# Lumen-Driver-X2.net
KiCad netlist of a schematic drawn in EAGLE
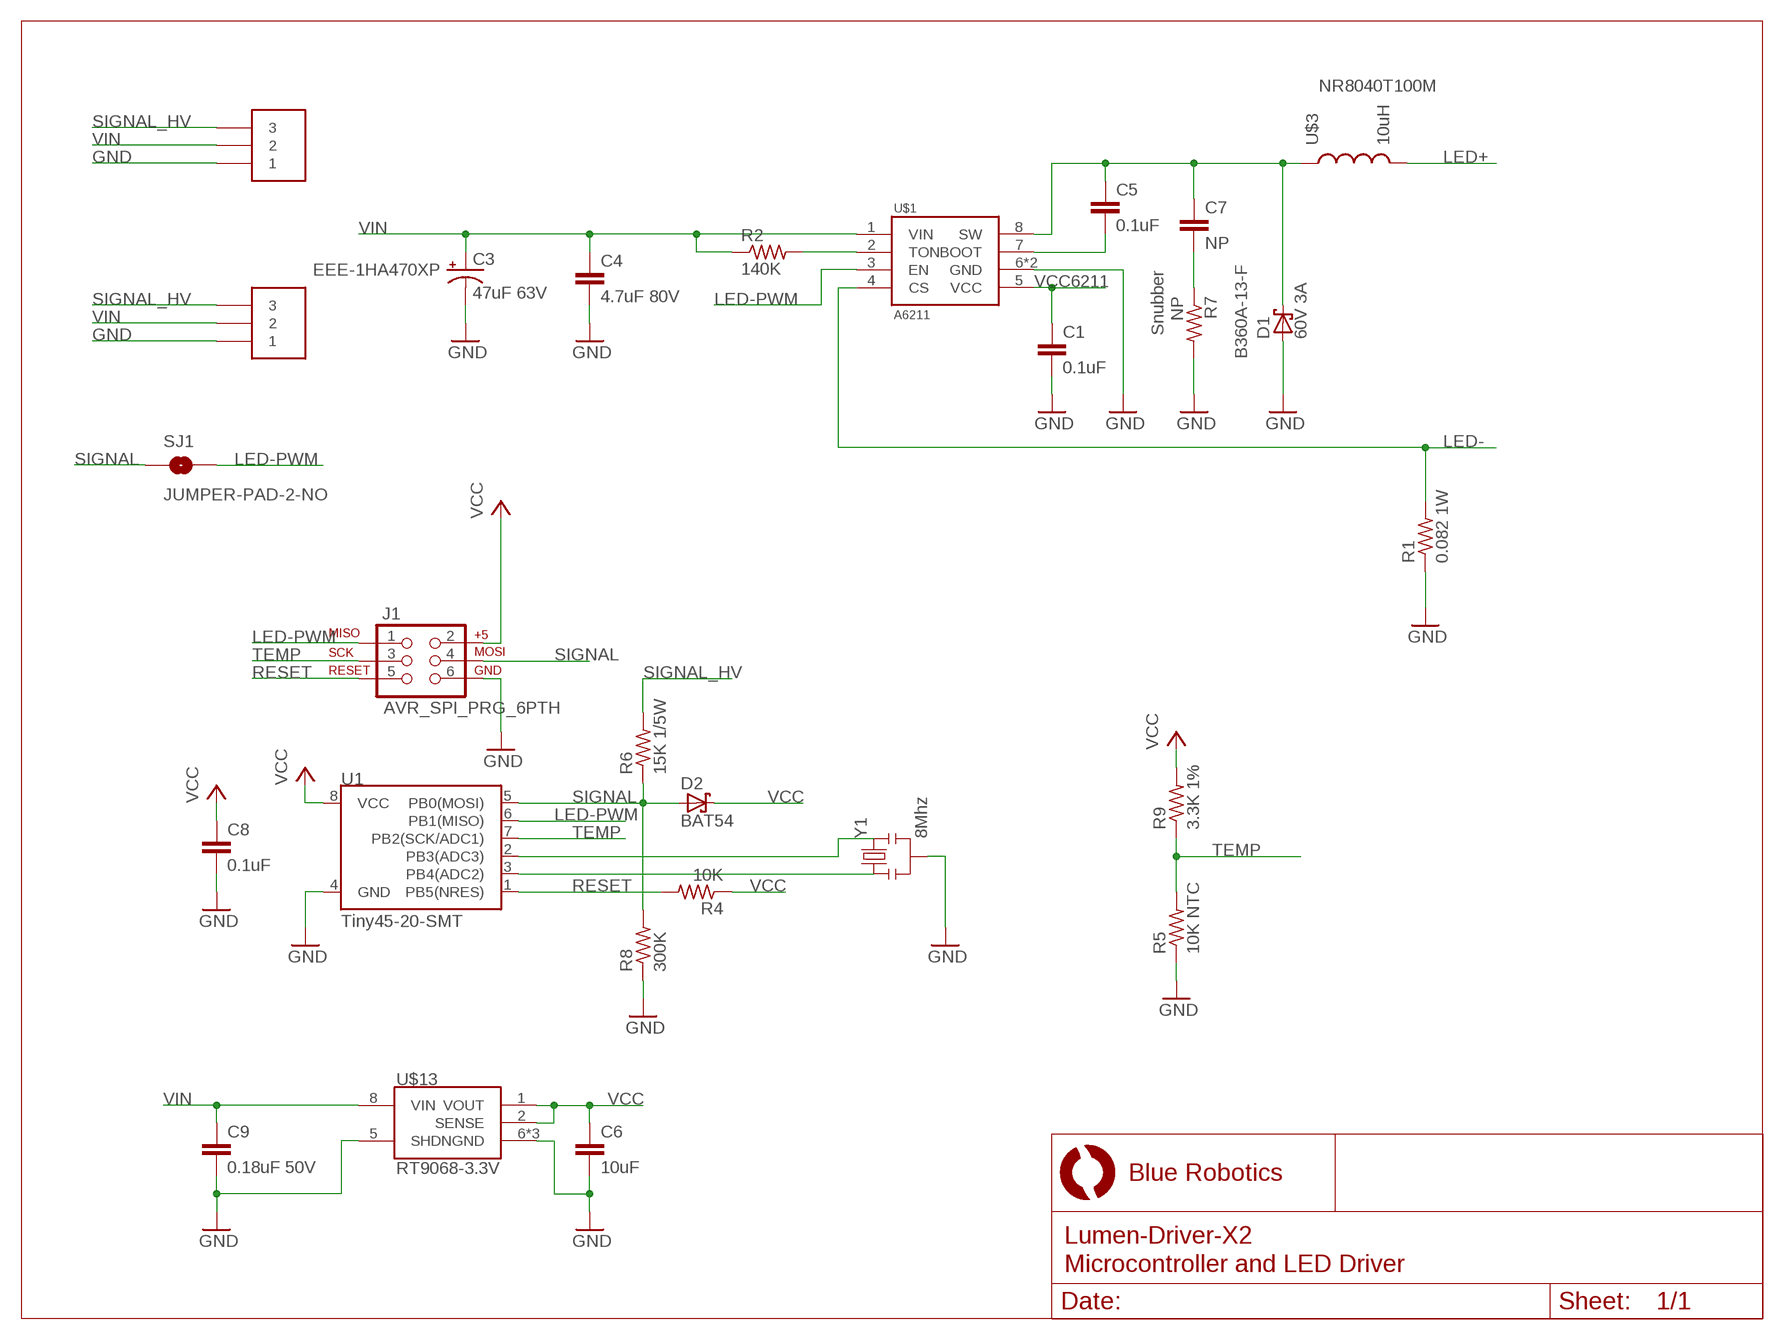
[diagram p0: schematic, sheet 1]

(export (version "E")
  (design (tool "Eeschema 10.0.6"))
  (components
    (comp (ref "C1")
      (value "0.1uF")
      (footprint "eagle-import:C0402")
      (libsource (lib "eagle-import") (part "CAPACITOR_0402"))
    )
    (comp (ref "C3")
      (value "47uF 63V")
      (footprint "eagle-import:PANASONIC_D")
      (libsource (lib "eagle-import") (part "CAP_POLD"))
    )
    (comp (ref "C4")
      (value "4.7uF 80V")
      (footprint "eagle-import:C1210")
      (libsource (lib "eagle-import") (part "C-EUC1210"))
    )
    (comp (ref "C5")
      (value "0.1uF")
      (footprint "eagle-import:C0402")
      (libsource (lib "eagle-import") (part "CAPACITOR_0402"))
    )
    (comp (ref "C6")
      (value "10uF")
      (footprint "eagle-import:C0603")
      (libsource (lib "eagle-import") (part "C-EUC0603"))
    )
    (comp (ref "C7")
      (value "NP")
      (footprint "eagle-import:C0603")
      (libsource (lib "eagle-import") (part "C-EUC0603"))
    )
    (comp (ref "C8")
      (value "0.1uF")
      (footprint "eagle-import:C0402")
      (libsource (lib "eagle-import") (part "CAPACITOR_0402"))
    )
    (comp (ref "C9")
      (value "0.18uF 50V")
      (footprint "eagle-import:C0805")
      (libsource (lib "eagle-import") (part "C-EUC0805"))
    )
    (comp (ref "D1")
      (value "60V 3A")
      (footprint "eagle-import:SMA")
      (libsource (lib "eagle-import") (part "DIODE-SCHOTTKYSMA"))
    )
    (comp (ref "D2")
      (value "BAT54")
      (footprint "eagle-import:SOD523")
      (libsource (lib "eagle-import") (part "DIODE-SCHOTTKYSOD523"))
    )
    (comp (ref "J1")
      (value "AVR_SPI_PRG_6PTH")
      (footprint "eagle-import:2X3")
      (libsource (lib "eagle-import") (part "AVR_SPI_PRG_6PTH"))
    )
    (comp (ref "R1")
      (value "0.082 1W")
      (footprint "eagle-import:R2512")
      (libsource (lib "eagle-import") (part "R-US_R2512"))
    )
    (comp (ref "R2")
      (value "140K")
      (footprint "eagle-import:R0402")
      (libsource (lib "eagle-import") (part "RESISTOR_0402"))
    )
    (comp (ref "R4")
      (value "10K")
      (footprint "eagle-import:R0402")
      (libsource (lib "eagle-import") (part "RESISTOR_0402"))
    )
    (comp (ref "R5")
      (value "10K NTC")
      (footprint "eagle-import:R0603")
      (libsource (lib "eagle-import") (part "R-US_R0603"))
    )
    (comp (ref "R6")
      (value "15K 1/5W")
      (footprint "eagle-import:R0402")
      (libsource (lib "eagle-import") (part "RESISTOR_0402"))
    )
    (comp (ref "R7")
      (value "NP")
      (footprint "eagle-import:R1206")
      (libsource (lib "eagle-import") (part "R-US_R1206"))
    )
    (comp (ref "R8")
      (value "300K")
      (footprint "eagle-import:R0402")
      (libsource (lib "eagle-import") (part "RESISTOR_0402"))
    )
    (comp (ref "R9")
      (value "3.3K 1%")
      (footprint "eagle-import:R0402")
      (libsource (lib "eagle-import") (part "RESISTOR_0402"))
    )
    (comp (ref "SJ1")
      (value "JUMPER-PAD-2-NO")
      (footprint "eagle-import:PAD-JUMPER-2-NO_NO_SILK")
      (libsource (lib "eagle-import") (part "JUMPER-PAD-2-NO"))
    )
    (comp (ref "U$1")
      (value "A6211")
      (footprint "eagle-import:SOIC8N-LJ")
      (libsource (lib "eagle-import") (part "A6211"))
    )
    (comp (ref "U$3")
      (value "10uH")
      (footprint "eagle-import:INDUCTOR-8040")
      (libsource (lib "eagle-import") (part "INDUCTOR8040"))
    )
    (comp (ref "U$11")
      (value "009176003032006")
      (footprint "eagle-import:AVX-9176-3POS")
      (libsource (lib "eagle-import") (part "HEADER-3AVX-9176"))
    )
    (comp (ref "U$12")
      (value "009176003032006")
      (footprint "eagle-import:AVX-9176-3POS")
      (libsource (lib "eagle-import") (part "HEADER-3AVX-9176"))
    )
    (comp (ref "U$13")
      (value "RT9068-3.3V")
      (footprint "eagle-import:SOIC8N-LJ")
      (libsource (lib "eagle-import") (part "VREG-RT9068SOP-8"))
    )
    (comp (ref "U1")
      (value "Tiny45-20-SMT")
      (footprint "eagle-import:SO08-EIAJ")
      (libsource (lib "eagle-import") (part "ATTINY45TINY45-20-SMT"))
    )
    (comp (ref "Y1")
      (value "8Mhz")
      (footprint "eagle-import:RESONATOR-SMD")
      (libsource (lib "eagle-import") (part "RESONATORSMD"))
    )
  )
  (nets
    (net (code "1") (name "/LED+") (class "Default")
      (node (ref "U$3") (pin "P$2") (pinfunction "2_P$2") (pintype "passive"))
    )
    (net (code "2") (name "/LED-") (class "Default")
      (node (ref "R1") (pin "2") (pinfunction "2_2") (pintype "passive"))
      (node (ref "U$1") (pin "4") (pinfunction "CS_4") (pintype "bidirectional"))
    )
    (net (code "3") (name "/LED-PWM") (class "Default")
      (node (ref "J1") (pin "1") (pinfunction "1_1") (pintype "passive"))
      (node (ref "SJ1") (pin "2") (pinfunction "2_2") (pintype "passive"))
      (node (ref "U$1") (pin "3") (pinfunction "EN_3") (pintype "bidirectional"))
      (node (ref "U1") (pin "6") (pinfunction "PB1(MISO)_6") (pintype "bidirectional"))
    )
    (net (code "4") (name "/RESET") (class "Default")
      (node (ref "J1") (pin "5") (pinfunction "5_5") (pintype "passive"))
      (node (ref "R4") (pin "2") (pinfunction "2_2") (pintype "passive"))
      (node (ref "U1") (pin "1") (pinfunction "PB5(NRES)_1") (pintype "bidirectional"))
    )
    (net (code "5") (name "/SIGNAL") (class "Default")
      (node (ref "D2") (pin "A") (pinfunction "A_A") (pintype "passive"))
      (node (ref "J1") (pin "4") (pinfunction "4_4") (pintype "passive"))
      (node (ref "R6") (pin "1") (pinfunction "1_1") (pintype "passive"))
      (node (ref "R8") (pin "2") (pinfunction "2_2") (pintype "passive"))
      (node (ref "SJ1") (pin "1") (pinfunction "1_1") (pintype "passive"))
      (node (ref "U1") (pin "5") (pinfunction "PB0(MOSI)_5") (pintype "bidirectional"))
    )
    (net (code "6") (name "/SIGNAL_HV") (class "Default")
      (node (ref "R6") (pin "2") (pinfunction "2_2") (pintype "passive"))
      (node (ref "U$11") (pin "3") (pinfunction "3_3") (pintype "bidirectional"))
      (node (ref "U$12") (pin "3") (pinfunction "3_3") (pintype "bidirectional"))
    )
    (net (code "7") (name "/TEMP") (class "Default")
      (node (ref "J1") (pin "3") (pinfunction "3_3") (pintype "passive"))
      (node (ref "R5") (pin "2") (pinfunction "2_2") (pintype "passive"))
      (node (ref "R9") (pin "1") (pinfunction "1_1") (pintype "passive"))
      (node (ref "U1") (pin "7") (pinfunction "PB2(SCK/ADC1)_7") (pintype "bidirectional"))
    )
    (net (code "8") (name "/VCC6211") (class "Default")
      (node (ref "C1") (pin "1") (pinfunction "1_1") (pintype "passive"))
      (node (ref "U$1") (pin "5") (pinfunction "VCC_5") (pintype "bidirectional"))
    )
    (net (code "9") (name "/VIN") (class "Default")
      (node (ref "C3") (pin "+") (pinfunction "+_+") (pintype "passive"))
      (node (ref "C4") (pin "1") (pinfunction "1_1") (pintype "passive"))
      (node (ref "C9") (pin "1") (pinfunction "1_1") (pintype "passive"))
      (node (ref "R2") (pin "1") (pinfunction "1_1") (pintype "passive"))
      (node (ref "U$1") (pin "1") (pinfunction "VIN_1") (pintype "bidirectional"))
      (node (ref "U$11") (pin "2") (pinfunction "2_2") (pintype "bidirectional"))
      (node (ref "U$12") (pin "2") (pinfunction "2_2") (pintype "bidirectional"))
      (node (ref "U$13") (pin "8") (pinfunction "VIN_8") (pintype "bidirectional"))
    )
    (net (code "10") (name "GND") (class "Default")
      (node (ref "C1") (pin "2") (pinfunction "2_2") (pintype "passive"))
      (node (ref "C3") (pin "-") (pinfunction "-_-") (pintype "passive"))
      (node (ref "C4") (pin "2") (pinfunction "2_2") (pintype "passive"))
      (node (ref "C6") (pin "2") (pinfunction "2_2") (pintype "passive"))
      (node (ref "C8") (pin "2") (pinfunction "2_2") (pintype "passive"))
      (node (ref "C9") (pin "2") (pinfunction "2_2") (pintype "passive"))
      (node (ref "D1") (pin "A") (pinfunction "A_A") (pintype "passive"))
      (node (ref "J1") (pin "6") (pinfunction "6_6") (pintype "passive"))
      (node (ref "R1") (pin "1") (pinfunction "1_1") (pintype "passive"))
      (node (ref "R5") (pin "1") (pinfunction "1_1") (pintype "passive"))
      (node (ref "R7") (pin "2") (pinfunction "2_2") (pintype "passive"))
      (node (ref "R8") (pin "1") (pinfunction "1_1") (pintype "passive"))
      (node (ref "U$1") (pin "6") (pinfunction "GND_6") (pintype "bidirectional"))
      (node (ref "U$1") (pin "PAD") (pinfunction "GND_PAD") (pintype "bidirectional"))
      (node (ref "U$11") (pin "1") (pinfunction "1_1") (pintype "bidirectional"))
      (node (ref "U$12") (pin "1") (pinfunction "1_1") (pintype "bidirectional"))
      (node (ref "U$13") (pin "5") (pinfunction "SHDN_5") (pintype "bidirectional"))
      (node (ref "U$13") (pin "6") (pinfunction "GND_6") (pintype "bidirectional"))
      (node (ref "U$13") (pin "7") (pinfunction "GND_7") (pintype "bidirectional"))
      (node (ref "U$13") (pin "PAD") (pinfunction "GND_PAD") (pintype "bidirectional"))
      (node (ref "U1") (pin "4") (pinfunction "GND_4") (pintype "bidirectional"))
      (node (ref "Y1") (pin "2") (pinfunction "2_2") (pintype "passive"))
    )
    (net (code "11") (name "Net-(C7-Pad2)") (class "Default")
      (node (ref "C7") (pin "2") (pinfunction "2_2") (pintype "passive"))
      (node (ref "R7") (pin "1") (pinfunction "1_1") (pintype "passive"))
    )
    (net (code "12") (name "Net-(U$1-BOOT)") (class "Default")
      (node (ref "C5") (pin "2") (pinfunction "2_2") (pintype "passive"))
      (node (ref "U$1") (pin "7") (pinfunction "BOOT_7") (pintype "bidirectional"))
    )
    (net (code "13") (name "Net-(U$1-SW)") (class "Default")
      (node (ref "C5") (pin "1") (pinfunction "1_1") (pintype "passive"))
      (node (ref "C7") (pin "1") (pinfunction "1_1") (pintype "passive"))
      (node (ref "D1") (pin "C") (pinfunction "C_C") (pintype "passive"))
      (node (ref "U$1") (pin "8") (pinfunction "SW_8") (pintype "bidirectional"))
      (node (ref "U$3") (pin "P$1") (pinfunction "1_P$1") (pintype "passive"))
    )
    (net (code "14") (name "Net-(U$1-TON)") (class "Default")
      (node (ref "R2") (pin "2") (pinfunction "2_2") (pintype "passive"))
      (node (ref "U$1") (pin "2") (pinfunction "TON_2") (pintype "bidirectional"))
    )
    (net (code "15") (name "Net-(U1-PB3(ADC3))") (class "Default")
      (node (ref "U1") (pin "2") (pinfunction "PB3(ADC3)_2") (pintype "bidirectional"))
      (node (ref "Y1") (pin "3") (pinfunction "3_3") (pintype "passive"))
    )
    (net (code "16") (name "Net-(U1-PB4(ADC2))") (class "Default")
      (node (ref "U1") (pin "3") (pinfunction "PB4(ADC2)_3") (pintype "bidirectional"))
      (node (ref "Y1") (pin "1") (pinfunction "1_1") (pintype "passive"))
    )
    (net (code "17") (name "VCC") (class "Default")
      (node (ref "C6") (pin "1") (pinfunction "1_1") (pintype "passive"))
      (node (ref "C8") (pin "1") (pinfunction "1_1") (pintype "passive"))
      (node (ref "D2") (pin "C") (pinfunction "C_C") (pintype "passive"))
      (node (ref "J1") (pin "2") (pinfunction "2_2") (pintype "passive"))
      (node (ref "R4") (pin "1") (pinfunction "1_1") (pintype "passive"))
      (node (ref "R9") (pin "2") (pinfunction "2_2") (pintype "passive"))
      (node (ref "U$13") (pin "1") (pinfunction "VOUT_1") (pintype "bidirectional"))
      (node (ref "U$13") (pin "2") (pinfunction "SENSE_2") (pintype "bidirectional"))
      (node (ref "U1") (pin "8") (pinfunction "VCC_8") (pintype "bidirectional"))
    )
  )
)
